# LoRa.net
KiCad netlist of a schematic drawn in Altium Designer
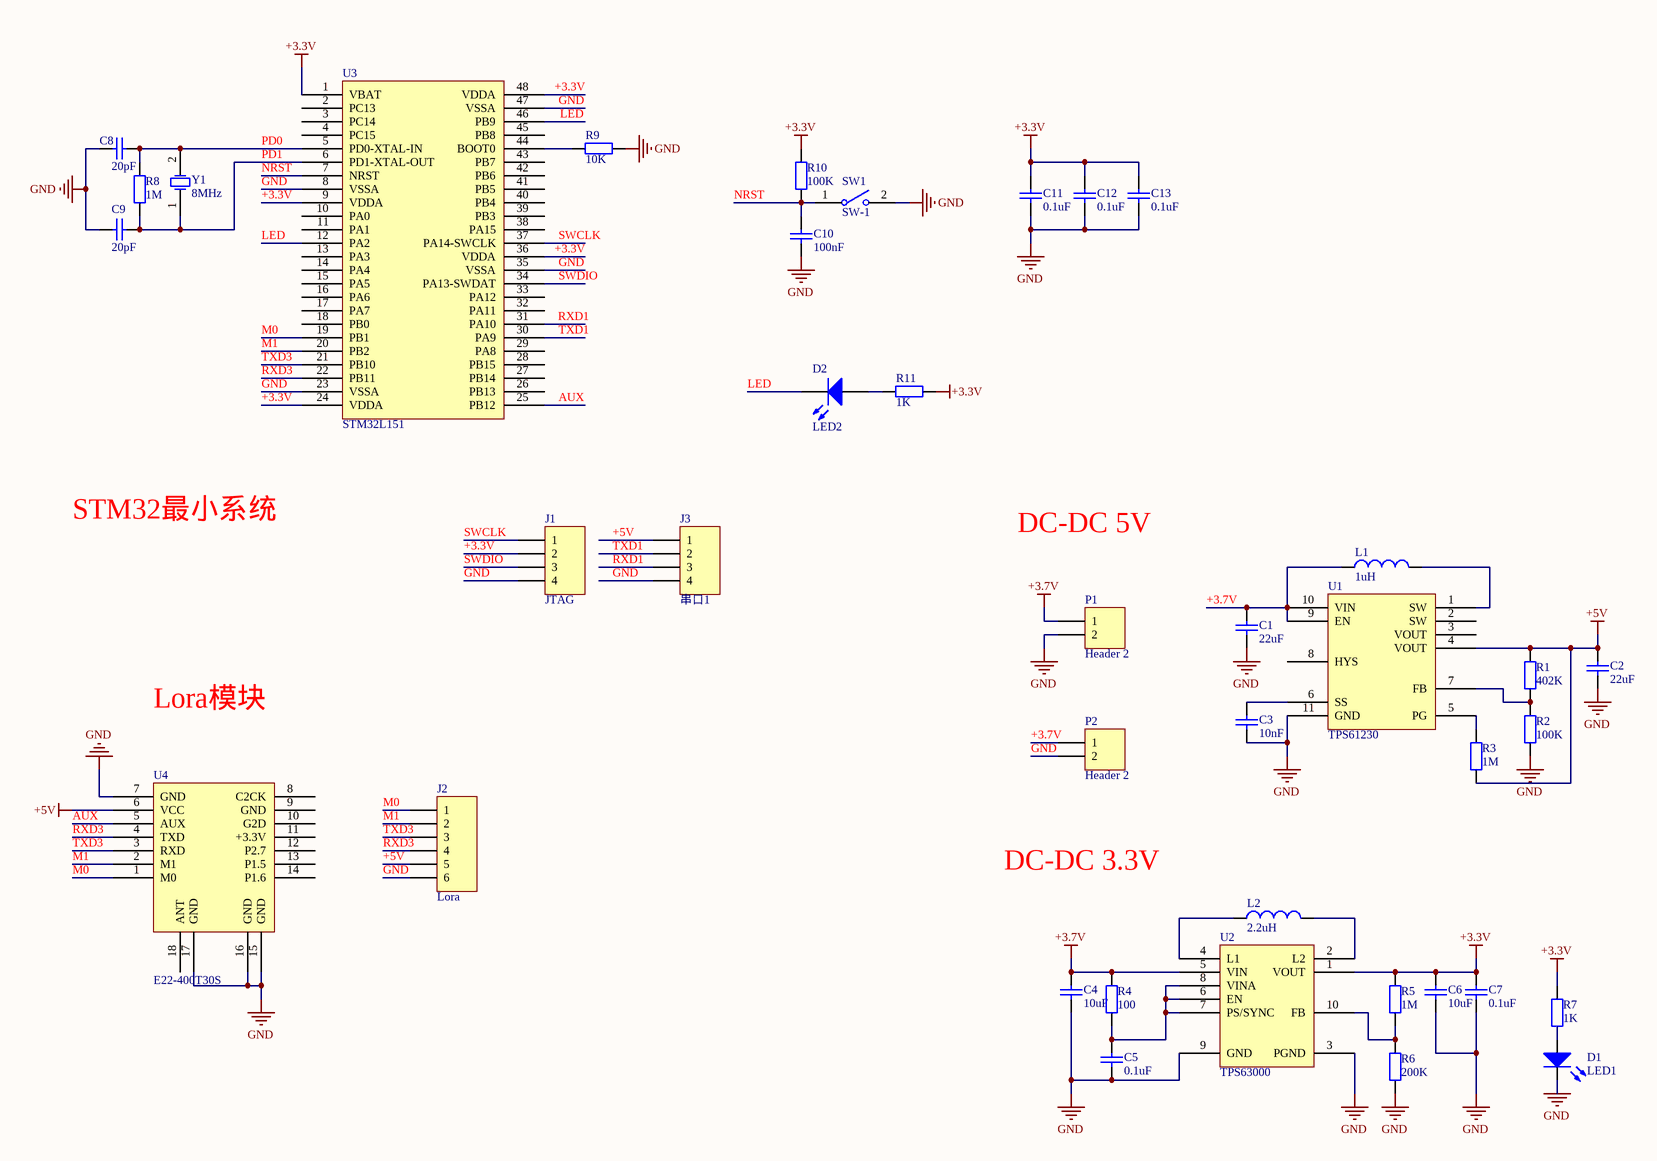
[diagram p0: LoRa.SchDoc]

(export (version "E")
  (design (tool "Eeschema 10.0.6"))
  (components
    (comp (ref "C1")
      (value "22uF")
      (footprint "0603C")
      (description "Capacitor")
      (fields (field (name "Comment") "Cap1") (field (name "PUBLISHER") "Altium Limited"))
      (libsource (lib "Miscellaneous Devices") (part "Cap"))
    )
    (comp (ref "C2")
      (value "22uF")
      (footprint "0603C")
      (description "Capacitor")
      (fields (field (name "Comment") "Cap2") (field (name "PUBLISHER") "Altium Limited"))
      (libsource (lib "Miscellaneous Devices") (part "Cap"))
    )
    (comp (ref "C3")
      (value "10nF")
      (footprint "0603C")
      (description "Capacitor")
      (fields (field (name "Comment") "Cap3") (field (name "PUBLISHER") "Altium Limited"))
      (libsource (lib "Miscellaneous Devices") (part "Cap"))
    )
    (comp (ref "C4")
      (value "10uF")
      (footprint "0603C")
      (description "Capacitor")
      (fields (field (name "Comment") "Cap4") (field (name "PUBLISHER") "Altium Limited"))
      (libsource (lib "Miscellaneous Devices") (part "Cap"))
    )
    (comp (ref "C5")
      (value "0.1uF")
      (footprint "0603C")
      (description "Capacitor")
      (fields (field (name "Comment") "Cap5") (field (name "PUBLISHER") "Altium Limited"))
      (libsource (lib "Miscellaneous Devices") (part "Cap"))
    )
    (comp (ref "C6")
      (value "10uF")
      (footprint "0603C")
      (description "Capacitor")
      (fields (field (name "Comment") "Cap6") (field (name "PUBLISHER") "Altium Limited"))
      (libsource (lib "Miscellaneous Devices") (part "Cap"))
    )
    (comp (ref "C7")
      (value "0.1uF")
      (footprint "0603C")
      (description "Capacitor")
      (fields (field (name "Comment") "Cap7") (field (name "PUBLISHER") "Altium Limited"))
      (libsource (lib "Miscellaneous Devices") (part "Cap"))
    )
    (comp (ref "C8")
      (value "20pF")
      (footprint "0603C")
      (description "Capacitor")
      (fields (field (name "Comment") "Cap8") (field (name "PUBLISHER") "Altium Limited"))
      (libsource (lib "Miscellaneous Devices") (part "Cap"))
    )
    (comp (ref "C9")
      (value "20pF")
      (footprint "0603C")
      (description "Capacitor")
      (fields (field (name "Comment") "Cap9") (field (name "PUBLISHER") "Altium Limited"))
      (libsource (lib "Miscellaneous Devices") (part "Cap"))
    )
    (comp (ref "C10")
      (value "100nF")
      (footprint "0603C")
      (description "Capacitor")
      (fields (field (name "Comment") "Cap10") (field (name "PUBLISHER") "Altium Limited"))
      (libsource (lib "Miscellaneous Devices") (part "Cap"))
    )
    (comp (ref "C11")
      (value "0.1uF")
      (footprint "0603C")
      (description "Capacitor")
      (fields (field (name "Comment") "Cap11") (field (name "PUBLISHER") "Altium Limited"))
      (libsource (lib "Miscellaneous Devices") (part "Cap"))
    )
    (comp (ref "C12")
      (value "0.1uF")
      (footprint "0603C")
      (description "Capacitor")
      (fields (field (name "Comment") "Cap12") (field (name "PUBLISHER") "Altium Limited"))
      (libsource (lib "Miscellaneous Devices") (part "Cap"))
    )
    (comp (ref "C13")
      (value "0.1uF")
      (footprint "0603C")
      (description "Capacitor")
      (fields (field (name "Comment") "Cap13") (field (name "PUBLISHER") "Altium Limited"))
      (libsource (lib "Miscellaneous Devices") (part "Cap"))
    )
    (comp (ref "D1")
      (value "LED1")
      (footprint "贴片二极管")
      (description "Typical RED GaAs LED")
      (fields (field (name "PUBLISHER") "Altium Limited"))
      (libsource (lib "Miscellaneous Devices") (part "LED1"))
    )
    (comp (ref "D2")
      (value "LED2")
      (footprint "贴片二极管")
      (description "Typical RED GaAs LED")
      (fields (field (name "PUBLISHER") "Altium Limited"))
      (libsource (lib "Miscellaneous Devices") (part "LED1"))
    )
    (comp (ref "J1")
      (value "JTAG")
      (footprint "HDR1X4")
      (description "Header, 4-Pin")
      (fields (field (name "PUBLISHER") "Altium Limited"))
      (libsource (lib "Miscellaneous Connectors") (part "Header 4"))
    )
    (comp (ref "J2")
      (value "Lora")
      (footprint "HDR1X6")
      (description "Header, 6-Pin")
      (fields (field (name "PUBLISHER") "Altium Limited"))
      (libsource (lib "Miscellaneous Connectors") (part "Header 6"))
    )
    (comp (ref "J3")
      (value "串口1")
      (footprint "HDR1X4")
      (description "Header, 4-Pin")
      (fields (field (name "PUBLISHER") "Altium Limited"))
      (libsource (lib "Miscellaneous Connectors") (part "Header 4"))
    )
    (comp (ref "L1")
      (value "1uH")
      (footprint "IND-SMD_L4.0-W4.0_SMNR4020")
      (description "Inductor")
      (fields (field (name "Comment") "Inductor1") (field (name "PUBLISHER") "Altium Limited"))
      (libsource (lib "Miscellaneous Devices") (part "Inductor"))
    )
    (comp (ref "L2")
      (value "2.2uH")
      (footprint "IND-SMD_L4.0-W4.0_SMNR4020")
      (description "Inductor")
      (fields (field (name "Comment") "Inductor2") (field (name "PUBLISHER") "Altium Limited"))
      (libsource (lib "Miscellaneous Devices") (part "Inductor"))
    )
    (comp (ref "P1")
      (value "Header 2")
      (footprint "HDR1X2")
      (description "Header, 2-Pin")
      (fields (field (name "PUBLISHER") "Altium Limited"))
      (libsource (lib "Miscellaneous Connectors") (part "Header 2"))
    )
    (comp (ref "P2")
      (value "Header 2")
      (footprint "HDR1X2")
      (description "Header, 2-Pin")
      (fields (field (name "PUBLISHER") "Altium Limited"))
      (libsource (lib "Miscellaneous Connectors") (part "Header 2"))
    )
    (comp (ref "R1")
      (value "402K")
      (footprint "0603R")
      (description "Resistor")
      (fields (field (name "Comment") "Res1") (field (name "PUBLISHER") "Altium Limited"))
      (libsource (lib "Miscellaneous Devices") (part "Res2"))
    )
    (comp (ref "R2")
      (value "100K")
      (footprint "0603R")
      (description "Resistor")
      (fields (field (name "Comment") "Res2") (field (name "PUBLISHER") "Altium Limited"))
      (libsource (lib "Miscellaneous Devices") (part "Res2"))
    )
    (comp (ref "R3")
      (value "1M")
      (footprint "0603R")
      (description "Resistor")
      (fields (field (name "Comment") "Res3") (field (name "PUBLISHER") "Altium Limited"))
      (libsource (lib "Miscellaneous Devices") (part "Res2"))
    )
    (comp (ref "R4")
      (value "100")
      (footprint "0603R")
      (description "Resistor")
      (fields (field (name "Comment") "Res4") (field (name "PUBLISHER") "Altium Limited"))
      (libsource (lib "Miscellaneous Devices") (part "Res2"))
    )
    (comp (ref "R5")
      (value "1M")
      (footprint "0603R")
      (description "Resistor")
      (fields (field (name "Comment") "Res5") (field (name "PUBLISHER") "Altium Limited"))
      (libsource (lib "Miscellaneous Devices") (part "Res2"))
    )
    (comp (ref "R6")
      (value "200K")
      (footprint "0603R")
      (description "Resistor")
      (fields (field (name "Comment") "Res6") (field (name "PUBLISHER") "Altium Limited"))
      (libsource (lib "Miscellaneous Devices") (part "Res2"))
    )
    (comp (ref "R7")
      (value "1K")
      (footprint "0603R")
      (description "Resistor")
      (fields (field (name "Comment") "Res7") (field (name "PUBLISHER") "Altium Limited"))
      (libsource (lib "Miscellaneous Devices") (part "Res2"))
    )
    (comp (ref "R8")
      (value "1M")
      (footprint "0603R")
      (description "Resistor")
      (fields (field (name "Comment") "Res8") (field (name "PUBLISHER") "Altium Limited"))
      (libsource (lib "Miscellaneous Devices") (part "Res2"))
    )
    (comp (ref "R9")
      (value "10K")
      (footprint "0603R")
      (description "Resistor")
      (fields (field (name "Comment") "Res9") (field (name "PUBLISHER") "Altium Limited"))
      (libsource (lib "") (part "Res2_1"))
    )
    (comp (ref "R10")
      (value "100K")
      (footprint "0603R")
      (description "Resistor")
      (fields (field (name "Comment") "Res10") (field (name "PUBLISHER") "Altium Limited"))
      (libsource (lib "Miscellaneous Devices") (part "Res2"))
    )
    (comp (ref "R11")
      (value "1K")
      (footprint "0603R")
      (description "Resistor")
      (fields (field (name "Comment") "Res11") (field (name "PUBLISHER") "Altium Limited"))
      (libsource (lib "") (part "Res2_1"))
    )
    (comp (ref "SW1") (value "SW-1") (footprint "SW-1") (libsource (lib "WuRenSouJiu") (part "SW-1")))
    (comp (ref "U1")
      (value "TPS61230")
      (footprint "VSON-10_L3.0-W3.0-P0.50-BL-EP")
      (libsource (lib "WuRenSouJiu") (part "TPS61230"))
    )
    (comp (ref "U2")
      (value "TPS63000")
      (footprint "SON-10_L3.1-W3.1-P0.50-BL-EP")
      (libsource (lib "WuRenSouJiu") (part "TPS63000"))
    )
    (comp (ref "U3")
      (value "STM32L151")
      (footprint "TQFP48")
      (libsource (lib "WuRenSouJiu") (part "STM32L151"))
    )
    (comp (ref "U4")
      (value "E22-400T30S")
      (footprint "PE32(915T30S)")
      (libsource (lib "WuRenSouJiu") (part "E22-400T30S"))
    )
    (comp (ref "Y1")
      (value "8MHz")
      (footprint "XTAL")
      (description "Crystal Oscillator")
      (fields (field (name "PUBLISHER") "Altium Limited"))
      (libsource (lib "Miscellaneous Devices") (part "XTAL"))
    )
  )
  (nets
    (net (code "1") (name "+3.3V") (class "Default")
      (node (ref "C11") (pin "1") (pinfunction "1_1") (pintype "passive"))
      (node (ref "C12") (pin "1") (pinfunction "1_1") (pintype "passive"))
      (node (ref "C13") (pin "1") (pinfunction "1_1") (pintype "passive"))
      (node (ref "C6") (pin "2") (pinfunction "2_2") (pintype "passive"))
      (node (ref "C7") (pin "2") (pinfunction "2_2") (pintype "passive"))
      (node (ref "J1") (pin "2") (pinfunction "2_2") (pintype "passive"))
      (node (ref "R10") (pin "2") (pinfunction "2_2") (pintype "passive"))
      (node (ref "R11") (pin "2") (pinfunction "2_2") (pintype "passive"))
      (node (ref "R5") (pin "2") (pinfunction "2_2") (pintype "passive"))
      (node (ref "R7") (pin "2") (pinfunction "2_2") (pintype "passive"))
      (node (ref "U2") (pin "1") (pinfunction "VOUT_1") (pintype "passive"))
      (node (ref "U3") (pin "1") (pinfunction "VBAT_1") (pintype "passive"))
      (node (ref "U3") (pin "24") (pinfunction "VDDA_24") (pintype "passive"))
      (node (ref "U3") (pin "36") (pinfunction "VDDA_36") (pintype "passive"))
      (node (ref "U3") (pin "48") (pinfunction "VDDA_48") (pintype "passive"))
      (node (ref "U3") (pin "9") (pinfunction "VDDA_9") (pintype "passive"))
    )
    (net (code "2") (name "+3.7V") (class "Default")
      (node (ref "C1") (pin "2") (pinfunction "2_2") (pintype "passive"))
      (node (ref "C4") (pin "2") (pinfunction "2_2") (pintype "passive"))
      (node (ref "L1") (pin "1") (pinfunction "1_1") (pintype "passive"))
      (node (ref "P1") (pin "1") (pinfunction "1_1") (pintype "passive"))
      (node (ref "P2") (pin "1") (pinfunction "1_1") (pintype "passive"))
      (node (ref "R4") (pin "2") (pinfunction "2_2") (pintype "passive"))
      (node (ref "U1") (pin "10") (pinfunction "VIN_10") (pintype "passive"))
      (node (ref "U1") (pin "9") (pinfunction "EN_9") (pintype "passive"))
      (node (ref "U2") (pin "5") (pinfunction "VIN_5") (pintype "passive"))
    )
    (net (code "3") (name "+5V") (class "Default")
      (node (ref "C2") (pin "2") (pinfunction "2_2") (pintype "passive"))
      (node (ref "J2") (pin "5") (pinfunction "5_5") (pintype "passive"))
      (node (ref "J3") (pin "1") (pinfunction "1_1") (pintype "passive"))
      (node (ref "R1") (pin "2") (pinfunction "2_2") (pintype "passive"))
      (node (ref "R3") (pin "1") (pinfunction "1_1") (pintype "passive"))
      (node (ref "U1") (pin "4") (pinfunction "VOUT_4") (pintype "passive"))
      (node (ref "U4") (pin "6") (pinfunction "VCC_6") (pintype "passive"))
    )
    (net (code "4") (name "/AUX") (class "Default")
      (node (ref "U3") (pin "25") (pinfunction "PB12_25") (pintype "passive"))
      (node (ref "U4") (pin "5") (pinfunction "AUX_5") (pintype "passive"))
    )
    (net (code "5") (name "/LED") (class "Default")
      (node (ref "D2") (pin "2") (pinfunction "K_2") (pintype "passive"))
      (node (ref "U3") (pin "12") (pinfunction "PA2_12") (pintype "passive"))
      (node (ref "U3") (pin "46") (pinfunction "PB9_46") (pintype "passive"))
    )
    (net (code "6") (name "/M0") (class "Default")
      (node (ref "J2") (pin "1") (pinfunction "1_1") (pintype "passive"))
      (node (ref "U3") (pin "19") (pinfunction "PB1_19") (pintype "passive"))
      (node (ref "U4") (pin "1") (pinfunction "M0_1") (pintype "passive"))
    )
    (net (code "7") (name "/M1") (class "Default")
      (node (ref "J2") (pin "2") (pinfunction "2_2") (pintype "passive"))
      (node (ref "U3") (pin "20") (pinfunction "PB2_20") (pintype "passive"))
      (node (ref "U4") (pin "2") (pinfunction "M1_2") (pintype "passive"))
    )
    (net (code "8") (name "/NRST") (class "Default")
      (node (ref "C10") (pin "1") (pinfunction "1_1") (pintype "passive"))
      (node (ref "R10") (pin "1") (pinfunction "1_1") (pintype "passive"))
      (node (ref "SW1") (pin "1") (pinfunction "COMMON_1") (pintype "passive"))
      (node (ref "U3") (pin "7") (pinfunction "NRST_7") (pintype "passive"))
    )
    (net (code "9") (name "/PD0") (class "Default")
      (node (ref "C8") (pin "1") (pinfunction "1_1") (pintype "passive"))
      (node (ref "R8") (pin "2") (pinfunction "2_2") (pintype "passive"))
      (node (ref "U3") (pin "5") (pinfunction "PD0-XTAL-IN_5") (pintype "passive"))
      (node (ref "Y1") (pin "2") (pinfunction "OSC2_2") (pintype "passive"))
    )
    (net (code "10") (name "/PD1") (class "Default")
      (node (ref "C9") (pin "1") (pinfunction "1_1") (pintype "passive"))
      (node (ref "R8") (pin "1") (pinfunction "1_1") (pintype "passive"))
      (node (ref "U3") (pin "6") (pinfunction "PD1-XTAL-OUT_6") (pintype "passive"))
      (node (ref "Y1") (pin "1") (pinfunction "OSC1_1") (pintype "passive"))
    )
    (net (code "11") (name "/RXD1") (class "Default")
      (node (ref "J3") (pin "3") (pinfunction "3_3") (pintype "passive"))
      (node (ref "U3") (pin "31") (pinfunction "PA10_31") (pintype "passive"))
    )
    (net (code "12") (name "/RXD3") (class "Default")
      (node (ref "J2") (pin "4") (pinfunction "4_4") (pintype "passive"))
      (node (ref "U3") (pin "22") (pinfunction "PB11_22") (pintype "passive"))
      (node (ref "U4") (pin "4") (pinfunction "TXD_4") (pintype "passive"))
    )
    (net (code "13") (name "/SWCLK") (class "Default")
      (node (ref "J1") (pin "1") (pinfunction "1_1") (pintype "passive"))
      (node (ref "U3") (pin "37") (pinfunction "PA14-SWCLK_37") (pintype "passive"))
    )
    (net (code "14") (name "/SWDIO") (class "Default")
      (node (ref "J1") (pin "3") (pinfunction "3_3") (pintype "passive"))
      (node (ref "U3") (pin "34") (pinfunction "PA13-SWDAT_34") (pintype "passive"))
    )
    (net (code "15") (name "/TXD1") (class "Default")
      (node (ref "J3") (pin "2") (pinfunction "2_2") (pintype "passive"))
      (node (ref "U3") (pin "30") (pinfunction "PA9_30") (pintype "passive"))
    )
    (net (code "16") (name "/TXD3") (class "Default")
      (node (ref "J2") (pin "3") (pinfunction "3_3") (pintype "passive"))
      (node (ref "U3") (pin "21") (pinfunction "PB10_21") (pintype "passive"))
      (node (ref "U4") (pin "3") (pinfunction "RXD_3") (pintype "passive"))
    )
    (net (code "17") (name "GND") (class "Default")
      (node (ref "C1") (pin "1") (pinfunction "1_1") (pintype "passive"))
      (node (ref "C10") (pin "2") (pinfunction "2_2") (pintype "passive"))
      (node (ref "C11") (pin "2") (pinfunction "2_2") (pintype "passive"))
      (node (ref "C12") (pin "2") (pinfunction "2_2") (pintype "passive"))
      (node (ref "C13") (pin "2") (pinfunction "2_2") (pintype "passive"))
      (node (ref "C2") (pin "1") (pinfunction "1_1") (pintype "passive"))
      (node (ref "C3") (pin "1") (pinfunction "1_1") (pintype "passive"))
      (node (ref "C4") (pin "1") (pinfunction "1_1") (pintype "passive"))
      (node (ref "C5") (pin "1") (pinfunction "1_1") (pintype "passive"))
      (node (ref "C6") (pin "1") (pinfunction "1_1") (pintype "passive"))
      (node (ref "C7") (pin "1") (pinfunction "1_1") (pintype "passive"))
      (node (ref "C8") (pin "2") (pinfunction "2_2") (pintype "passive"))
      (node (ref "C9") (pin "2") (pinfunction "2_2") (pintype "passive"))
      (node (ref "D1") (pin "2") (pinfunction "K_2") (pintype "passive"))
      (node (ref "J1") (pin "4") (pinfunction "4_4") (pintype "passive"))
      (node (ref "J2") (pin "6") (pinfunction "6_6") (pintype "passive"))
      (node (ref "J3") (pin "4") (pinfunction "4_4") (pintype "passive"))
      (node (ref "P1") (pin "2") (pinfunction "2_2") (pintype "passive"))
      (node (ref "P2") (pin "2") (pinfunction "2_2") (pintype "passive"))
      (node (ref "R2") (pin "1") (pinfunction "1_1") (pintype "passive"))
      (node (ref "R6") (pin "1") (pinfunction "1_1") (pintype "passive"))
      (node (ref "R9") (pin "2") (pinfunction "2_2") (pintype "passive"))
      (node (ref "SW1") (pin "2") (pinfunction "COMMON_2") (pintype "passive"))
      (node (ref "U1") (pin "11") (pinfunction "GND_11") (pintype "passive"))
      (node (ref "U2") (pin "3") (pinfunction "PGND_3") (pintype "passive"))
      (node (ref "U2") (pin "9") (pinfunction "GND_9") (pintype "passive"))
      (node (ref "U3") (pin "23") (pinfunction "VSSA_23") (pintype "passive"))
      (node (ref "U3") (pin "35") (pinfunction "VSSA_35") (pintype "passive"))
      (node (ref "U3") (pin "47") (pinfunction "VSSA_47") (pintype "passive"))
      (node (ref "U3") (pin "8") (pinfunction "VSSA_8") (pintype "passive"))
      (node (ref "U4") (pin "15") (pinfunction "GND_15") (pintype "passive"))
      (node (ref "U4") (pin "16") (pinfunction "GND_16") (pintype "passive"))
      (node (ref "U4") (pin "17") (pinfunction "GND_17") (pintype "passive"))
      (node (ref "U4") (pin "7") (pinfunction "GND_7") (pintype "passive"))
    )
    (net (code "18") (name "Net-(D1-A)") (class "Default")
      (node (ref "D1") (pin "1") (pinfunction "A_1") (pintype "passive"))
      (node (ref "R7") (pin "1") (pinfunction "1_1") (pintype "passive"))
    )
    (net (code "19") (name "Net-(D2-A)") (class "Default")
      (node (ref "D2") (pin "1") (pinfunction "A_1") (pintype "passive"))
      (node (ref "R11") (pin "1") (pinfunction "1_1") (pintype "passive"))
    )
    (net (code "20") (name "Net-(L1-Pad2)") (class "Default")
      (node (ref "L1") (pin "2") (pinfunction "2_2") (pintype "passive"))
      (node (ref "U1") (pin "1") (pinfunction "SW_1") (pintype "passive"))
    )
    (net (code "21") (name "Net-(U1-FB)") (class "Default")
      (node (ref "R1") (pin "1") (pinfunction "1_1") (pintype "passive"))
      (node (ref "R2") (pin "2") (pinfunction "2_2") (pintype "passive"))
      (node (ref "U1") (pin "7") (pinfunction "FB_7") (pintype "passive"))
    )
    (net (code "22") (name "Net-(U1-PG)") (class "Default")
      (node (ref "R3") (pin "2") (pinfunction "2_2") (pintype "passive"))
      (node (ref "U1") (pin "5") (pinfunction "PG_5") (pintype "passive"))
    )
    (net (code "23") (name "Net-(U1-SS)") (class "Default")
      (node (ref "C3") (pin "2") (pinfunction "2_2") (pintype "passive"))
      (node (ref "U1") (pin "6") (pinfunction "SS_6") (pintype "passive"))
    )
    (net (code "24") (name "Net-(U2-EN)") (class "Default")
      (node (ref "C5") (pin "2") (pinfunction "2_2") (pintype "passive"))
      (node (ref "R4") (pin "1") (pinfunction "1_1") (pintype "passive"))
      (node (ref "U2") (pin "6") (pinfunction "EN_6") (pintype "passive"))
      (node (ref "U2") (pin "7") (pinfunction "PS/SYNC_7") (pintype "passive"))
      (node (ref "U2") (pin "8") (pinfunction "VINA_8") (pintype "passive"))
    )
    (net (code "25") (name "Net-(U2-FB)") (class "Default")
      (node (ref "R5") (pin "1") (pinfunction "1_1") (pintype "passive"))
      (node (ref "R6") (pin "2") (pinfunction "2_2") (pintype "passive"))
      (node (ref "U2") (pin "10") (pinfunction "FB_10") (pintype "passive"))
    )
    (net (code "26") (name "Net-(U2-L1)") (class "Default")
      (node (ref "L2") (pin "1") (pinfunction "1_1") (pintype "passive"))
      (node (ref "U2") (pin "4") (pinfunction "L1_4") (pintype "passive"))
    )
    (net (code "27") (name "Net-(U2-L2)") (class "Default")
      (node (ref "L2") (pin "2") (pinfunction "2_2") (pintype "passive"))
      (node (ref "U2") (pin "2") (pinfunction "L2_2") (pintype "passive"))
    )
    (net (code "28") (name "Net-(U3-BOOT0)") (class "Default")
      (node (ref "R9") (pin "1") (pinfunction "1_1") (pintype "passive"))
      (node (ref "U3") (pin "44") (pinfunction "BOOT0_44") (pintype "passive"))
    )
    (net (code "29") (name "unconnected-(U1-HYS-Pad8)") (class "Default")
      (node (ref "U1") (pin "8") (pinfunction "HYS_8") (pintype "passive"))
    )
    (net (code "30") (name "unconnected-(U1-SW-Pad2)") (class "Default")
      (node (ref "U1") (pin "2") (pinfunction "SW_2") (pintype "passive"))
    )
    (net (code "31") (name "unconnected-(U1-VOUT-Pad3)") (class "Default")
      (node (ref "U1") (pin "3") (pinfunction "VOUT_3") (pintype "passive"))
    )
    (net (code "32") (name "unconnected-(U3-PA0-Pad10)") (class "Default")
      (node (ref "U3") (pin "10") (pinfunction "PA0_10") (pintype "passive"))
    )
    (net (code "33") (name "unconnected-(U3-PA1-Pad11)") (class "Default")
      (node (ref "U3") (pin "11") (pinfunction "PA1_11") (pintype "passive"))
    )
    (net (code "34") (name "unconnected-(U3-PA3-Pad13)") (class "Default")
      (node (ref "U3") (pin "13") (pinfunction "PA3_13") (pintype "passive"))
    )
    (net (code "35") (name "unconnected-(U3-PA4-Pad14)") (class "Default")
      (node (ref "U3") (pin "14") (pinfunction "PA4_14") (pintype "passive"))
    )
    (net (code "36") (name "unconnected-(U3-PA5-Pad15)") (class "Default")
      (node (ref "U3") (pin "15") (pinfunction "PA5_15") (pintype "passive"))
    )
    (net (code "37") (name "unconnected-(U3-PA6-Pad16)") (class "Default")
      (node (ref "U3") (pin "16") (pinfunction "PA6_16") (pintype "passive"))
    )
    (net (code "38") (name "unconnected-(U3-PA7-Pad17)") (class "Default")
      (node (ref "U3") (pin "17") (pinfunction "PA7_17") (pintype "passive"))
    )
    (net (code "39") (name "unconnected-(U3-PA8-Pad29)") (class "Default")
      (node (ref "U3") (pin "29") (pinfunction "PA8_29") (pintype "passive"))
    )
    (net (code "40") (name "unconnected-(U3-PA11-Pad32)") (class "Default")
      (node (ref "U3") (pin "32") (pinfunction "PA11_32") (pintype "passive"))
    )
    (net (code "41") (name "unconnected-(U3-PA12-Pad33)") (class "Default")
      (node (ref "U3") (pin "33") (pinfunction "PA12_33") (pintype "passive"))
    )
    (net (code "42") (name "unconnected-(U3-PA15-Pad38)") (class "Default")
      (node (ref "U3") (pin "38") (pinfunction "PA15_38") (pintype "passive"))
    )
    (net (code "43") (name "unconnected-(U3-PB0-Pad18)") (class "Default")
      (node (ref "U3") (pin "18") (pinfunction "PB0_18") (pintype "passive"))
    )
    (net (code "44") (name "unconnected-(U3-PB3-Pad39)") (class "Default")
      (node (ref "U3") (pin "39") (pinfunction "PB3_39") (pintype "passive"))
    )
    (net (code "45") (name "unconnected-(U3-PB4-Pad40)") (class "Default")
      (node (ref "U3") (pin "40") (pinfunction "PB4_40") (pintype "passive"))
    )
    (net (code "46") (name "unconnected-(U3-PB5-Pad41)") (class "Default")
      (node (ref "U3") (pin "41") (pinfunction "PB5_41") (pintype "passive"))
    )
    (net (code "47") (name "unconnected-(U3-PB6-Pad42)") (class "Default")
      (node (ref "U3") (pin "42") (pinfunction "PB6_42") (pintype "passive"))
    )
    (net (code "48") (name "unconnected-(U3-PB7-Pad43)") (class "Default")
      (node (ref "U3") (pin "43") (pinfunction "PB7_43") (pintype "passive"))
    )
    (net (code "49") (name "unconnected-(U3-PB8-Pad45)") (class "Default")
      (node (ref "U3") (pin "45") (pinfunction "PB8_45") (pintype "passive"))
    )
    (net (code "50") (name "unconnected-(U3-PB13-Pad26)") (class "Default")
      (node (ref "U3") (pin "26") (pinfunction "PB13_26") (pintype "passive"))
    )
    (net (code "51") (name "unconnected-(U3-PB14-Pad27)") (class "Default")
      (node (ref "U3") (pin "27") (pinfunction "PB14_27") (pintype "passive"))
    )
    (net (code "52") (name "unconnected-(U3-PB15-Pad28)") (class "Default")
      (node (ref "U3") (pin "28") (pinfunction "PB15_28") (pintype "passive"))
    )
    (net (code "53") (name "unconnected-(U3-PC13-Pad2)") (class "Default")
      (node (ref "U3") (pin "2") (pinfunction "PC13_2") (pintype "passive"))
    )
    (net (code "54") (name "unconnected-(U3-PC14-Pad3)") (class "Default")
      (node (ref "U3") (pin "3") (pinfunction "PC14_3") (pintype "passive"))
    )
    (net (code "55") (name "unconnected-(U3-PC15-Pad4)") (class "Default")
      (node (ref "U3") (pin "4") (pinfunction "PC15_4") (pintype "passive"))
    )
    (net (code "56") (name "unconnected-(U4-+3.3V-Pad11)") (class "Default")
      (node (ref "U4") (pin "11") (pinfunction "+3.3V_11") (pintype "passive"))
    )
    (net (code "57") (name "unconnected-(U4-ANT-Pad18)") (class "Default")
      (node (ref "U4") (pin "18") (pinfunction "ANT_18") (pintype "passive"))
    )
    (net (code "58") (name "unconnected-(U4-C2CK-Pad8)") (class "Default")
      (node (ref "U4") (pin "8") (pinfunction "C2CK_8") (pintype "passive"))
    )
    (net (code "59") (name "unconnected-(U4-G2D-Pad10)") (class "Default")
      (node (ref "U4") (pin "10") (pinfunction "G2D_10") (pintype "passive"))
    )
    (net (code "60") (name "unconnected-(U4-GND-Pad9)") (class "Default")
      (node (ref "U4") (pin "9") (pinfunction "GND_9") (pintype "passive"))
    )
    (net (code "61") (name "unconnected-(U4-P1.5-Pad13)") (class "Default")
      (node (ref "U4") (pin "13") (pinfunction "P1.5_13") (pintype "passive"))
    )
    (net (code "62") (name "unconnected-(U4-P1.6-Pad14)") (class "Default")
      (node (ref "U4") (pin "14") (pinfunction "P1.6_14") (pintype "passive"))
    )
    (net (code "63") (name "unconnected-(U4-P2.7-Pad12)") (class "Default")
      (node (ref "U4") (pin "12") (pinfunction "P2.7_12") (pintype "passive"))
    )
  )
)
